# ultra-violet-tooth-sensor-mk-1_1.net
KiCad netlist of a schematic drawn in EAGLE
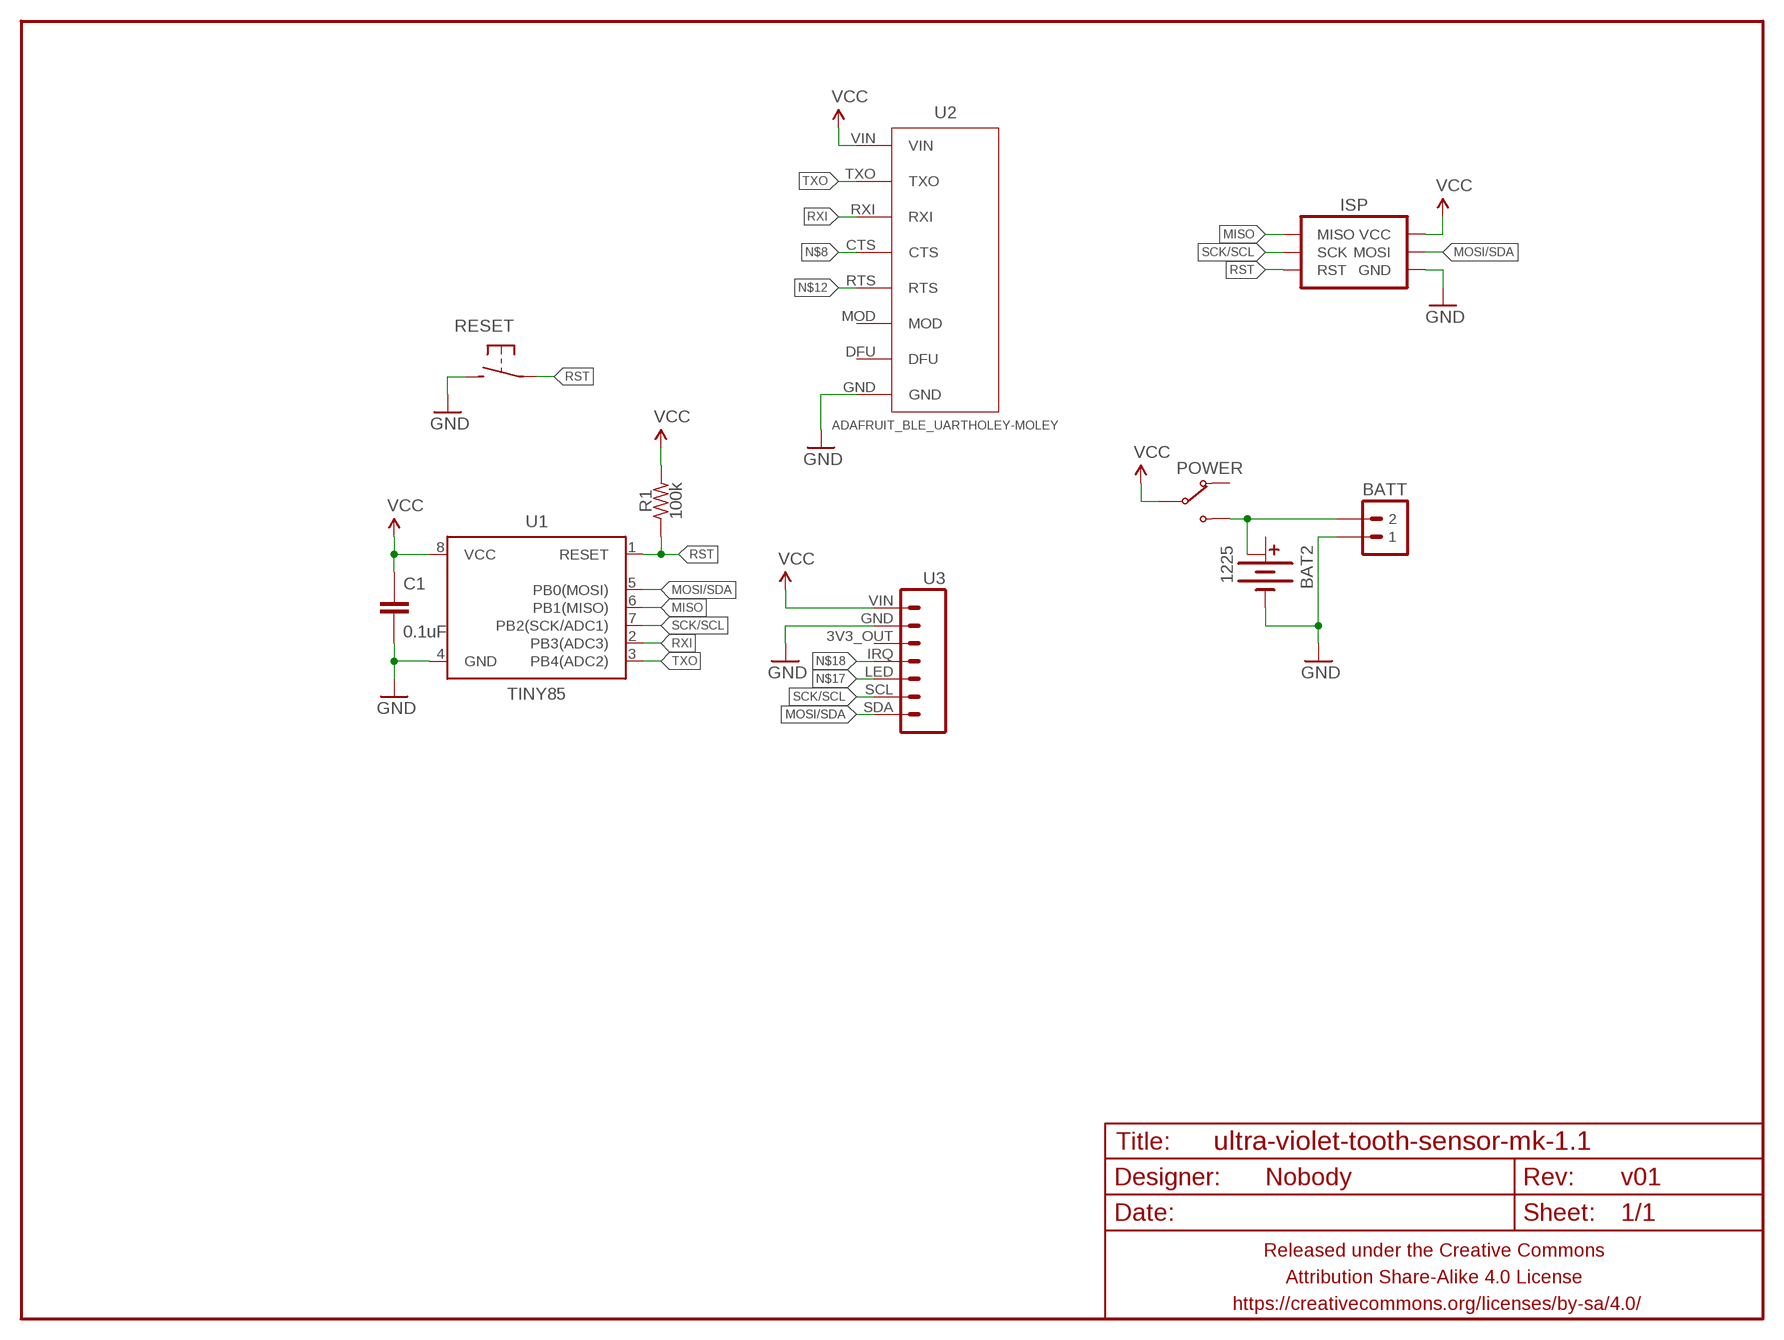
[diagram p0: schematic, sheet 1]

(export (version "E")
  (design (tool "Eeschema 10.0.6"))
  (components
    (comp (ref "BAT2")
      (value "1225")
      (footprint "eagle-import:BATTCON_12MM")
      (libsource (lib "eagle-import") (part "BATTERY-COINCR1225_SMD"))
    )
    (comp (ref "BATT")
      (value "M02PTH-CENTERED-R+")
      (footprint "eagle-import:1X02-CENTER-R+")
      (libsource (lib "eagle-import") (part "M02PTH-CENTERED-R+"))
    )
    (comp (ref "C1")
      (value "0.1uF")
      (footprint "eagle-import:C025-024X044")
      (libsource (lib "eagle-import") (part "CAPACITOR-CERAMIC025-024X044"))
    )
    (comp (ref "FRAME1")
      (value "FRAME-LETTERNO_PACKAGE")
      (footprint "eagle-import:DUMMY")
      (fields (field (name "DESIGNER") "Nobody"))
      (libsource (lib "eagle-import") (part "FRAME-LETTERNO_PACKAGE"))
    )
    (comp (ref "ISP")
      (value "AVR_SPI_PRG_6PTH")
      (footprint "eagle-import:2X3")
      (libsource (lib "eagle-import") (part "AVR_SPI_PRG_6PTH"))
    )
    (comp (ref "POWER")
      (value "SWITCH-SPDTPTH-RA-2.54MM")
      (footprint "eagle-import:SPDT-RA-2.54MM")
      (libsource (lib "eagle-import") (part "SWITCH-SPDTPTH-RA-2.54MM"))
    )
    (comp (ref "R1")
      (value "100k")
      (footprint "eagle-import:RESISTOR-AXIAL-PTH-7.62MM")
      (libsource (lib "eagle-import") (part "RESISTORPTH-AXIAL-7.62MM"))
    )
    (comp (ref "RESET")
      (value "SPST-NO-TACT3MM-RA")
      (footprint "eagle-import:TACTILE-PTH-SIDE")
      (libsource (lib "eagle-import") (part "SPST-NO-TACT3MM-RA"))
    )
    (comp (ref "U1")
      (value "TINY85")
      (footprint "eagle-import:DIP08")
      (libsource (lib "eagle-import") (part "ATTINY45TINY85-20-DIP"))
    )
    (comp (ref "U2")
      (value "ADAFRUIT_BLE_UARTHOLEY-MOLEY")
      (footprint "eagle-import:ADAFRUIT_BLE_UART_HOLEY")
      (libsource (lib "eagle-import") (part "ADAFRUIT_BLE_UARTHOLEY-MOLEY"))
    )
    (comp (ref "U3")
      (value "ADAFRUIT-SI1145-BREAKOUT")
      (footprint "eagle-import:ADAFRUIT-SI1145-BREAKOUT")
      (libsource (lib "eagle-import") (part "ADAFRUIT-SI1145-BREAKOUT"))
    )
  )
  (nets
    (net (code "1") (name "GND") (class "Default")
      (node (ref "BAT2") (pin "GND") (pinfunction "-_GND") (pintype "bidirectional"))
      (node (ref "BATT") (pin "1") (pinfunction "1_1") (pintype "passive"))
      (node (ref "C1") (pin "2") (pinfunction "2_2") (pintype "passive"))
      (node (ref "ISP") (pin "6") (pinfunction "GND_6") (pintype "passive"))
      (node (ref "RESET") (pin "2") (pinfunction "2_2") (pintype "passive"))
      (node (ref "U1") (pin "4") (pinfunction "GND_4") (pintype "bidirectional"))
      (node (ref "U2") (pin "GND") (pinfunction "GND_GND") (pintype "bidirectional"))
      (node (ref "U3") (pin "GND") (pinfunction "GND_GND") (pintype "passive"))
    )
    (net (code "2") (name "MISO") (class "Default")
      (node (ref "ISP") (pin "1") (pinfunction "MISO_1") (pintype "passive"))
      (node (ref "U1") (pin "6") (pinfunction "PB1(MISO)_6") (pintype "bidirectional"))
    )
    (net (code "3") (name "MOSI{slash}SDA") (class "Default")
      (node (ref "ISP") (pin "4") (pinfunction "MOSI_4") (pintype "passive"))
      (node (ref "U1") (pin "5") (pinfunction "PB0(MOSI)_5") (pintype "bidirectional"))
      (node (ref "U3") (pin "SDA") (pinfunction "SDA_SDA") (pintype "passive"))
    )
    (net (code "4") (name "N$8") (class "Default")
      (node (ref "U2") (pin "CTS") (pinfunction "CTS_CTS") (pintype "bidirectional"))
    )
    (net (code "5") (name "N$12") (class "Default")
      (node (ref "U2") (pin "RTS") (pinfunction "RTS_RTS") (pintype "bidirectional"))
    )
    (net (code "6") (name "N$17") (class "Default")
      (node (ref "U3") (pin "LED") (pinfunction "LED_LED") (pintype "passive"))
    )
    (net (code "7") (name "N$18") (class "Default")
      (node (ref "U3") (pin "IRQ") (pinfunction "IRQ_IRQ") (pintype "passive"))
    )
    (net (code "8") (name "Net-(BAT2-+1)") (class "Default")
      (node (ref "BAT2") (pin "PWR@2") (pinfunction "+1_PWR@2") (pintype "bidirectional"))
      (node (ref "BATT") (pin "2") (pinfunction "2_2") (pintype "passive"))
      (node (ref "POWER") (pin "3") (pinfunction "NO_3") (pintype "passive"))
    )
    (net (code "9") (name "RST") (class "Default")
      (node (ref "ISP") (pin "5") (pinfunction "RST_5") (pintype "passive"))
      (node (ref "R1") (pin "P$1") (pinfunction "1_P$1") (pintype "passive"))
      (node (ref "RESET") (pin "1") (pinfunction "1_1") (pintype "passive"))
      (node (ref "U1") (pin "1") (pinfunction "RESET_1") (pintype "bidirectional"))
    )
    (net (code "10") (name "RXI") (class "Default")
      (node (ref "U1") (pin "2") (pinfunction "PB3(ADC3)_2") (pintype "bidirectional"))
      (node (ref "U2") (pin "RXI") (pinfunction "RXI_RXI") (pintype "bidirectional"))
    )
    (net (code "11") (name "SCK{slash}SCL") (class "Default")
      (node (ref "ISP") (pin "3") (pinfunction "SCK_3") (pintype "passive"))
      (node (ref "U1") (pin "7") (pinfunction "PB2(SCK/ADC1)_7") (pintype "bidirectional"))
      (node (ref "U3") (pin "SCL") (pinfunction "SCL_SCL") (pintype "passive"))
    )
    (net (code "12") (name "TXO") (class "Default")
      (node (ref "U1") (pin "3") (pinfunction "PB4(ADC2)_3") (pintype "bidirectional"))
      (node (ref "U2") (pin "TXO") (pinfunction "TXO_TXO") (pintype "bidirectional"))
    )
    (net (code "13") (name "VCC") (class "Default")
      (node (ref "C1") (pin "1") (pinfunction "1_1") (pintype "passive"))
      (node (ref "ISP") (pin "2") (pinfunction "VCC_2") (pintype "passive"))
      (node (ref "POWER") (pin "2") (pinfunction "COM_2") (pintype "passive"))
      (node (ref "R1") (pin "P$2") (pinfunction "2_P$2") (pintype "passive"))
      (node (ref "U1") (pin "8") (pinfunction "VCC_8") (pintype "bidirectional"))
      (node (ref "U2") (pin "VIN") (pinfunction "VIN_VIN") (pintype "bidirectional"))
      (node (ref "U3") (pin "VIN") (pinfunction "VIN_VIN") (pintype "passive"))
    )
    (net (code "14") (name "unconnected-(BAT2-+-PadPWR@1)") (class "Default")
      (node (ref "BAT2") (pin "PWR@1") (pinfunction "+_PWR@1") (pintype "bidirectional"))
    )
    (net (code "15") (name "unconnected-(POWER-NC-Pad1)") (class "Default")
      (node (ref "POWER") (pin "1") (pinfunction "NC_1") (pintype "passive"))
    )
    (net (code "16") (name "unconnected-(U2-PadDFU)") (class "Default")
      (node (ref "U2") (pin "DFU") (pinfunction "DFU_DFU") (pintype "bidirectional"))
    )
    (net (code "17") (name "unconnected-(U2-PadMOD)") (class "Default")
      (node (ref "U2") (pin "MOD") (pinfunction "MOD_MOD") (pintype "bidirectional"))
    )
    (net (code "18") (name "unconnected-(U3-Pad3V3_OUT)") (class "Default")
      (node (ref "U3") (pin "3V3_OUT") (pinfunction "3V3_OUT_3V3_OUT") (pintype "passive"))
    )
  )
)
